# metal_detector.net
KiCad netlist of a schematic drawn in EAGLE
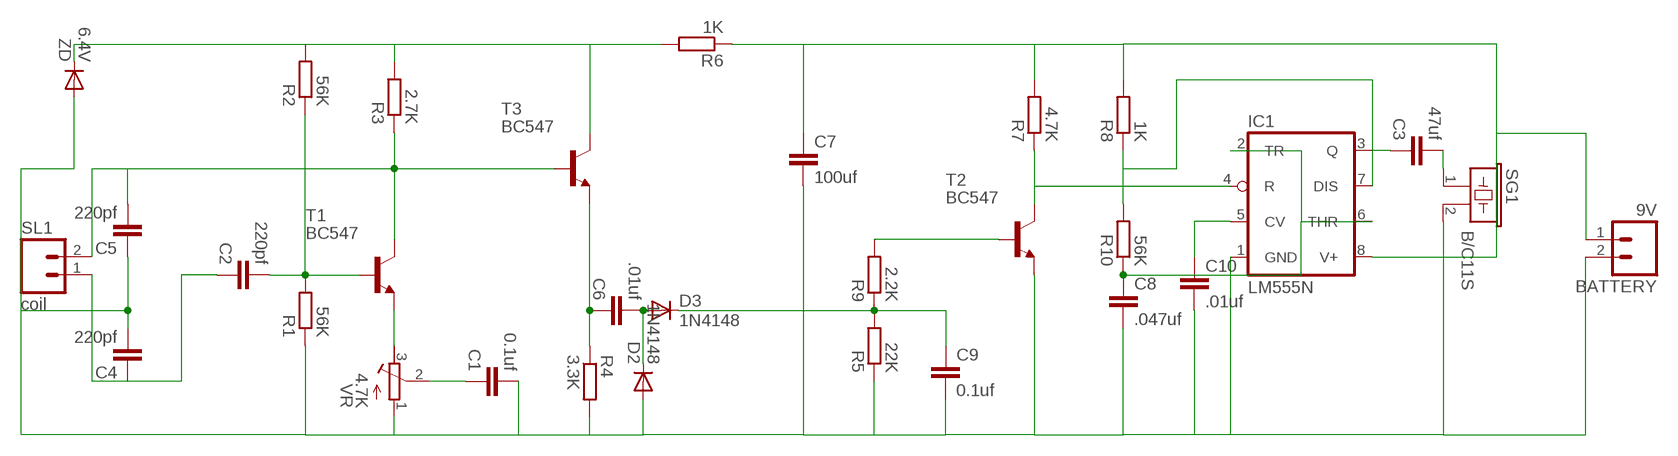
[diagram p0: schematic, sheet 1]

(export (version "E")
  (design (tool "Eeschema 10.0.6"))
  (components
    (comp (ref "BATTERY")
      (value "9V")
      (footprint "eagle-import:02P")
      (libsource (lib "eagle-import") (part "M02"))
    )
    (comp (ref "C1")
      (value "0.1uf")
      (footprint "eagle-import:C2.5-4")
      (libsource (lib "eagle-import") (part "C2.5/4"))
    )
    (comp (ref "C2")
      (value "220pf")
      (footprint "eagle-import:C2.5-4")
      (libsource (lib "eagle-import") (part "C2.5/4"))
    )
    (comp (ref "C3")
      (value "47uf")
      (footprint "eagle-import:C2.5-4")
      (libsource (lib "eagle-import") (part "C2.5/4"))
    )
    (comp (ref "C4")
      (value "220pf")
      (footprint "eagle-import:C2.5-4")
      (libsource (lib "eagle-import") (part "C2.5/4"))
    )
    (comp (ref "C5")
      (value "220pf")
      (footprint "eagle-import:C2.5-4")
      (libsource (lib "eagle-import") (part "C2.5/4"))
    )
    (comp (ref "C6")
      (value ".01uf")
      (footprint "eagle-import:C2.5-4")
      (libsource (lib "eagle-import") (part "C2.5/4"))
    )
    (comp (ref "C7")
      (value "100uf")
      (footprint "eagle-import:C2.5-4")
      (libsource (lib "eagle-import") (part "C2.5/4"))
    )
    (comp (ref "C8")
      (value ".047uf")
      (footprint "eagle-import:C2.5-4")
      (libsource (lib "eagle-import") (part "C2.5/4"))
    )
    (comp (ref "C9")
      (value "0.1uf")
      (footprint "eagle-import:C2.5-4")
      (libsource (lib "eagle-import") (part "C2.5/4"))
    )
    (comp (ref "C10")
      (value ".01uf")
      (footprint "eagle-import:C2.5-4")
      (libsource (lib "eagle-import") (part "C2.5/4"))
    )
    (comp (ref "D2")
      (value "1N4148")
      (footprint "eagle-import:DO41-10")
      (libsource (lib "eagle-import") (part "1N4004"))
    )
    (comp (ref "D3")
      (value "1N4148")
      (footprint "eagle-import:DO41-10")
      (libsource (lib "eagle-import") (part "1N4004"))
    )
    (comp (ref "IC1")
      (value "LM555N")
      (footprint "eagle-import:DIL08")
      (libsource (lib "eagle-import") (part "555NLM"))
    )
    (comp (ref "R1")
      (value "56K")
      (footprint "eagle-import:0204_7")
      (libsource (lib "eagle-import") (part "R-EU_0204/7"))
    )
    (comp (ref "R2")
      (value "56K")
      (footprint "eagle-import:0204_7")
      (libsource (lib "eagle-import") (part "R-EU_0204/7"))
    )
    (comp (ref "R3")
      (value "2.7K")
      (footprint "eagle-import:0204_7")
      (libsource (lib "eagle-import") (part "R-EU_0204/7"))
    )
    (comp (ref "R4")
      (value "3.3K")
      (footprint "eagle-import:0204_7")
      (libsource (lib "eagle-import") (part "R-EU_0204/7"))
    )
    (comp (ref "R5")
      (value "22K")
      (footprint "eagle-import:0204_7")
      (libsource (lib "eagle-import") (part "R-EU_0204/7"))
    )
    (comp (ref "R6")
      (value "1K")
      (footprint "eagle-import:0204_7")
      (libsource (lib "eagle-import") (part "R-EU_0204/7"))
    )
    (comp (ref "R7")
      (value "4.7K")
      (footprint "eagle-import:0204_7")
      (libsource (lib "eagle-import") (part "R-EU_0204/7"))
    )
    (comp (ref "R8")
      (value "1K")
      (footprint "eagle-import:0204_7")
      (libsource (lib "eagle-import") (part "R-EU_0204/7"))
    )
    (comp (ref "R9")
      (value "2.2K")
      (footprint "eagle-import:0204_7")
      (libsource (lib "eagle-import") (part "R-EU_0204/7"))
    )
    (comp (ref "R10")
      (value "56K")
      (footprint "eagle-import:0204_7")
      (libsource (lib "eagle-import") (part "R-EU_0204/7"))
    )
    (comp (ref "SG1")
      (value "B/C11S")
      (footprint "eagle-import:B_C11S")
      (libsource (lib "eagle-import") (part "B/C11S"))
    )
    (comp (ref "SL1")
      (value "coil")
      (footprint "eagle-import:02P")
      (libsource (lib "eagle-import") (part "M02"))
    )
    (comp (ref "T1")
      (value "BC547")
      (footprint "eagle-import:TO92")
      (libsource (lib "eagle-import") (part "BC547"))
    )
    (comp (ref "T2")
      (value "BC547")
      (footprint "eagle-import:TO92")
      (libsource (lib "eagle-import") (part "BC547"))
    )
    (comp (ref "T3")
      (value "BC547")
      (footprint "eagle-import:TO92")
      (libsource (lib "eagle-import") (part "BC547"))
    )
    (comp (ref "VR")
      (value "4.7K")
      (footprint "eagle-import:RTRIM64P")
      (libsource (lib "eagle-import") (part "R-TRIMM64P"))
    )
    (comp (ref "ZD")
      (value "6.4V")
      (footprint "eagle-import:DO41-10")
      (libsource (lib "eagle-import") (part "1N4004"))
    )
  )
  (nets
    (net (code "1") (name "Net-(C2-Pad1)") (class "Default")
      (node (ref "C2") (pin "1") (pinfunction "1_1") (pintype "passive"))
      (node (ref "C4") (pin "1") (pinfunction "1_1") (pintype "passive"))
      (node (ref "SL1") (pin "1") (pinfunction "1_1") (pintype "passive"))
    )
    (net (code "2") (name "Net-(C3-Pad2)") (class "Default")
      (node (ref "C3") (pin "2") (pinfunction "2_2") (pintype "passive"))
      (node (ref "SG1") (pin "1") (pinfunction "1_1") (pintype "passive"))
    )
    (net (code "3") (name "Net-(C6-Pad2)") (class "Default")
      (node (ref "C6") (pin "2") (pinfunction "2_2") (pintype "passive"))
      (node (ref "D2") (pin "C") (pinfunction "C_C") (pintype "passive"))
      (node (ref "D3") (pin "A") (pinfunction "A_A") (pintype "passive"))
    )
    (net (code "4") (name "Net-(C9-Pad1)") (class "Default")
      (node (ref "C9") (pin "1") (pinfunction "1_1") (pintype "passive"))
      (node (ref "D3") (pin "C") (pinfunction "C_C") (pintype "passive"))
      (node (ref "R5") (pin "2") (pinfunction "2_2") (pintype "passive"))
      (node (ref "R9") (pin "1") (pinfunction "1_1") (pintype "passive"))
    )
    (net (code "5") (name "Net-(IC1-CV)") (class "Default")
      (node (ref "C10") (pin "1") (pinfunction "1_1") (pintype "passive"))
      (node (ref "IC1") (pin "5") (pinfunction "CV_5") (pintype "input"))
    )
    (net (code "6") (name "Net-(IC1-DIS)") (class "Default")
      (node (ref "IC1") (pin "7") (pinfunction "DIS_7") (pintype "input"))
      (node (ref "R10") (pin "2") (pinfunction "2_2") (pintype "passive"))
      (node (ref "R8") (pin "1") (pinfunction "1_1") (pintype "passive"))
    )
    (net (code "7") (name "Net-(IC1-GND)") (class "Default")
      (node (ref "BATTERY") (pin "2") (pinfunction "2_2") (pintype "passive"))
      (node (ref "C1") (pin "2") (pinfunction "2_2") (pintype "passive"))
      (node (ref "C10") (pin "2") (pinfunction "2_2") (pintype "passive"))
      (node (ref "C4") (pin "2") (pinfunction "2_2") (pintype "passive"))
      (node (ref "C5") (pin "1") (pinfunction "1_1") (pintype "passive"))
      (node (ref "C7") (pin "2") (pinfunction "2_2") (pintype "passive"))
      (node (ref "C8") (pin "2") (pinfunction "2_2") (pintype "passive"))
      (node (ref "C9") (pin "2") (pinfunction "2_2") (pintype "passive"))
      (node (ref "D2") (pin "A") (pinfunction "A_A") (pintype "passive"))
      (node (ref "IC1") (pin "1") (pinfunction "GND_1") (pintype "power_in"))
      (node (ref "R1") (pin "1") (pinfunction "1_1") (pintype "passive"))
      (node (ref "R4") (pin "2") (pinfunction "2_2") (pintype "passive"))
      (node (ref "R5") (pin "1") (pinfunction "1_1") (pintype "passive"))
      (node (ref "SG1") (pin "2") (pinfunction "2_2") (pintype "passive"))
      (node (ref "T2") (pin "1") (pinfunction "E_1") (pintype "passive"))
      (node (ref "VR") (pin "1") (pinfunction "E_1") (pintype "passive"))
      (node (ref "ZD") (pin "A") (pinfunction "A_A") (pintype "passive"))
    )
    (net (code "8") (name "Net-(IC1-Q)") (class "Default")
      (node (ref "C3") (pin "1") (pinfunction "1_1") (pintype "passive"))
      (node (ref "IC1") (pin "3") (pinfunction "Q_3") (pintype "output"))
    )
    (net (code "9") (name "Net-(IC1-R)") (class "Default")
      (node (ref "IC1") (pin "4") (pinfunction "R_4") (pintype "input"))
      (node (ref "R7") (pin "1") (pinfunction "1_1") (pintype "passive"))
      (node (ref "T2") (pin "3") (pinfunction "C_3") (pintype "passive"))
    )
    (net (code "10") (name "Net-(IC1-THR)") (class "Default")
      (node (ref "C8") (pin "1") (pinfunction "1_1") (pintype "passive"))
      (node (ref "IC1") (pin "2") (pinfunction "TR_2") (pintype "input"))
      (node (ref "IC1") (pin "6") (pinfunction "THR_6") (pintype "input"))
      (node (ref "R10") (pin "1") (pinfunction "1_1") (pintype "passive"))
    )
    (net (code "11") (name "Net-(IC1-V+)") (class "Default")
      (node (ref "BATTERY") (pin "1") (pinfunction "1_1") (pintype "passive"))
      (node (ref "C7") (pin "1") (pinfunction "1_1") (pintype "passive"))
      (node (ref "IC1") (pin "8") (pinfunction "V+_8") (pintype "power_in"))
      (node (ref "R6") (pin "1") (pinfunction "1_1") (pintype "passive"))
      (node (ref "R7") (pin "2") (pinfunction "2_2") (pintype "passive"))
      (node (ref "R8") (pin "2") (pinfunction "2_2") (pintype "passive"))
    )
    (net (code "12") (name "Net-(T1-B)") (class "Default")
      (node (ref "C2") (pin "2") (pinfunction "2_2") (pintype "passive"))
      (node (ref "R1") (pin "2") (pinfunction "2_2") (pintype "passive"))
      (node (ref "R2") (pin "1") (pinfunction "1_1") (pintype "passive"))
      (node (ref "T1") (pin "2") (pinfunction "B_2") (pintype "passive"))
    )
    (net (code "13") (name "Net-(T1-C)") (class "Default")
      (node (ref "C5") (pin "2") (pinfunction "2_2") (pintype "passive"))
      (node (ref "R3") (pin "1") (pinfunction "1_1") (pintype "passive"))
      (node (ref "SL1") (pin "2") (pinfunction "2_2") (pintype "passive"))
      (node (ref "T1") (pin "3") (pinfunction "C_3") (pintype "passive"))
      (node (ref "T3") (pin "2") (pinfunction "B_2") (pintype "passive"))
    )
    (net (code "14") (name "Net-(T1-E)") (class "Default")
      (node (ref "T1") (pin "1") (pinfunction "E_1") (pintype "passive"))
      (node (ref "VR") (pin "3") (pinfunction "A_3") (pintype "passive"))
    )
    (net (code "15") (name "Net-(T2-B)") (class "Default")
      (node (ref "R9") (pin "2") (pinfunction "2_2") (pintype "passive"))
      (node (ref "T2") (pin "2") (pinfunction "B_2") (pintype "passive"))
    )
    (net (code "16") (name "Net-(T3-C)") (class "Default")
      (node (ref "R2") (pin "2") (pinfunction "2_2") (pintype "passive"))
      (node (ref "R3") (pin "2") (pinfunction "2_2") (pintype "passive"))
      (node (ref "R6") (pin "2") (pinfunction "2_2") (pintype "passive"))
      (node (ref "T3") (pin "3") (pinfunction "C_3") (pintype "passive"))
      (node (ref "ZD") (pin "C") (pinfunction "C_C") (pintype "passive"))
    )
    (net (code "17") (name "Net-(T3-E)") (class "Default")
      (node (ref "C6") (pin "1") (pinfunction "1_1") (pintype "passive"))
      (node (ref "R4") (pin "1") (pinfunction "1_1") (pintype "passive"))
      (node (ref "T3") (pin "1") (pinfunction "E_1") (pintype "passive"))
    )
    (net (code "18") (name "Net-(VR-S)") (class "Default")
      (node (ref "C1") (pin "1") (pinfunction "1_1") (pintype "passive"))
      (node (ref "VR") (pin "2") (pinfunction "S_2") (pintype "passive"))
    )
  )
)
